# Connectors.net
KiCad netlist of a schematic drawn in Altium Designer
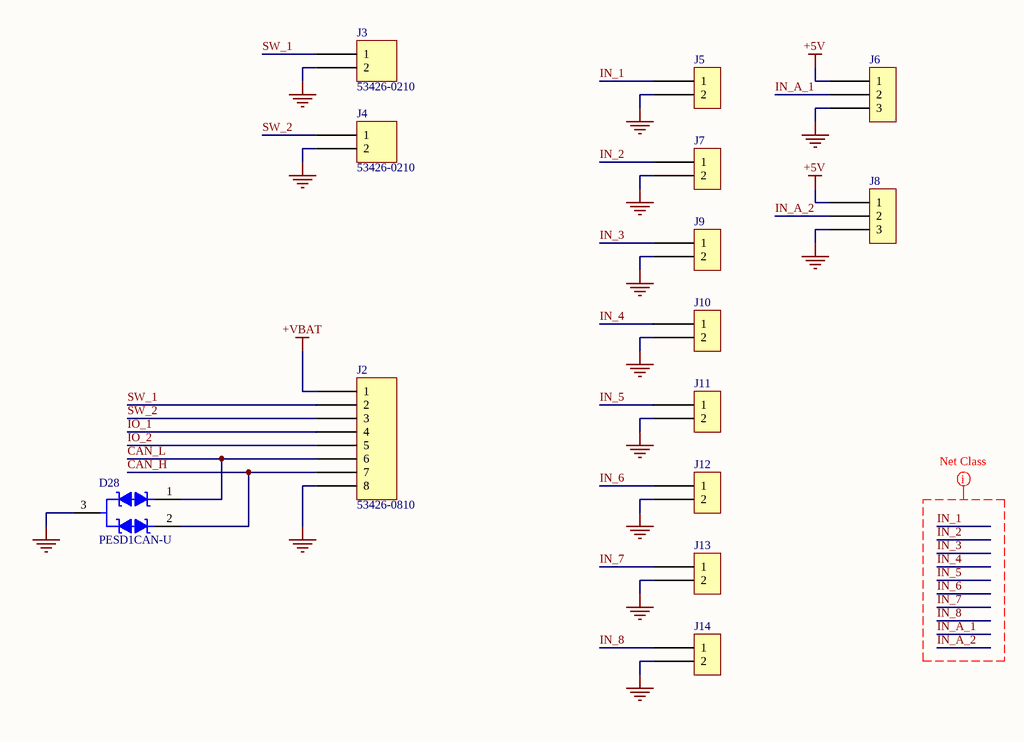
[diagram p0: Connectors.SchDoc]

(export (version "E")
  (design (tool "Eeschema 10.0.6"))
  (components
    (comp (ref "D28")
      (value "PESD1CAN-U")
      (footprint "SOT65P210X110-3N")
      (libsource (lib "CANio") (part "PESD1CAN-U"))
    )
    (comp (ref "J2")
      (value "53426-0810")
      (footprint "53426-0810")
      (description "Molex Mini-Lock™ 53426")
      (libsource (lib "Connectors") (part "53426-0810"))
    )
    (comp (ref "J3")
      (value "53426-0210")
      (footprint "53426-0210")
      (description "Molex Mini-Lock™ 53426")
      (libsource (lib "Connectors") (part "53426-0210"))
    )
    (comp (ref "J4")
      (value "53426-0210")
      (footprint "53426-0210")
      (description "Molex Mini-Lock™ 53426")
      (libsource (lib "Connectors") (part "53426-0210"))
    )
    (comp (ref "J5")
      (value "Wire-2-0.7mm")
      (footprint "WIRE-2-0.7mm")
      (libsource (lib "CANwheel") (part "Wire-2-0.7mm"))
    )
    (comp (ref "J6")
      (value "Wire-3-0.7mm")
      (footprint "WIRE-3-0.7mm")
      (libsource (lib "CANwheel") (part "Wire-3-0.7mm"))
    )
    (comp (ref "J7")
      (value "Wire-2-0.7mm")
      (footprint "WIRE-2-0.7mm")
      (libsource (lib "CANwheel") (part "Wire-2-0.7mm"))
    )
    (comp (ref "J8")
      (value "Wire-3-0.7mm")
      (footprint "WIRE-3-0.7mm")
      (libsource (lib "CANwheel") (part "Wire-3-0.7mm"))
    )
    (comp (ref "J9")
      (value "Wire-2-0.7mm")
      (footprint "WIRE-2-0.7mm")
      (libsource (lib "CANwheel") (part "Wire-2-0.7mm"))
    )
    (comp (ref "J10")
      (value "Wire-2-0.7mm")
      (footprint "WIRE-2-0.7mm")
      (libsource (lib "CANwheel") (part "Wire-2-0.7mm"))
    )
    (comp (ref "J11")
      (value "Wire-2-0.7mm")
      (footprint "WIRE-2-0.7mm")
      (libsource (lib "CANwheel") (part "Wire-2-0.7mm"))
    )
    (comp (ref "J12")
      (value "Wire-2-0.7mm")
      (footprint "WIRE-2-0.7mm")
      (libsource (lib "CANwheel") (part "Wire-2-0.7mm"))
    )
    (comp (ref "J13")
      (value "Wire-2-0.7mm")
      (footprint "WIRE-2-0.7mm")
      (libsource (lib "CANwheel") (part "Wire-2-0.7mm"))
    )
    (comp (ref "J14")
      (value "Wire-2-0.7mm")
      (footprint "WIRE-2-0.7mm")
      (libsource (lib "CANwheel") (part "Wire-2-0.7mm"))
    )
  )
  (nets
    (net (code "1") (name "+5V") (class "Default")
      (node (ref "J6") (pin "1") (pinfunction "1_1") (pintype "passive"))
      (node (ref "J8") (pin "1") (pinfunction "1_1") (pintype "passive"))
    )
    (net (code "2") (name "+VBAT") (class "Default")
      (node (ref "J2") (pin "1") (pinfunction "1_1") (pintype "passive"))
    )
    (net (code "3") (name "/CAN_H") (class "Default")
      (node (ref "D28") (pin "2") (pinfunction "2_2") (pintype "passive"))
      (node (ref "J2") (pin "7") (pinfunction "7_7") (pintype "passive"))
    )
    (net (code "4") (name "/CAN_L") (class "Default")
      (node (ref "D28") (pin "1") (pinfunction "1_1") (pintype "passive"))
      (node (ref "J2") (pin "6") (pinfunction "6_6") (pintype "passive"))
    )
    (net (code "5") (name "/IN_1") (class "Default")
      (node (ref "J5") (pin "1") (pinfunction "1_1") (pintype "passive"))
    )
    (net (code "6") (name "/IN_2") (class "Default")
      (node (ref "J7") (pin "1") (pinfunction "1_1") (pintype "passive"))
    )
    (net (code "7") (name "/IN_3") (class "Default")
      (node (ref "J9") (pin "1") (pinfunction "1_1") (pintype "passive"))
    )
    (net (code "8") (name "/IN_4") (class "Default")
      (node (ref "J10") (pin "1") (pinfunction "1_1") (pintype "passive"))
    )
    (net (code "9") (name "/IN_5") (class "Default")
      (node (ref "J11") (pin "1") (pinfunction "1_1") (pintype "passive"))
    )
    (net (code "10") (name "/IN_6") (class "Default")
      (node (ref "J12") (pin "1") (pinfunction "1_1") (pintype "passive"))
    )
    (net (code "11") (name "/IN_7") (class "Default")
      (node (ref "J13") (pin "1") (pinfunction "1_1") (pintype "passive"))
    )
    (net (code "12") (name "/IN_8") (class "Default")
      (node (ref "J14") (pin "1") (pinfunction "1_1") (pintype "passive"))
    )
    (net (code "13") (name "/IN_A_1") (class "Default")
      (node (ref "J6") (pin "2") (pinfunction "2_2") (pintype "passive"))
    )
    (net (code "14") (name "/IN_A_2") (class "Default")
      (node (ref "J8") (pin "2") (pinfunction "2_2") (pintype "passive"))
    )
    (net (code "15") (name "/IO_1") (class "Default")
      (node (ref "J2") (pin "4") (pinfunction "4_4") (pintype "passive"))
    )
    (net (code "16") (name "/IO_2") (class "Default")
      (node (ref "J2") (pin "5") (pinfunction "5_5") (pintype "passive"))
    )
    (net (code "17") (name "/SW_1") (class "Default")
      (node (ref "J2") (pin "2") (pinfunction "2_2") (pintype "passive"))
      (node (ref "J3") (pin "1") (pinfunction "1_1") (pintype "passive"))
    )
    (net (code "18") (name "/SW_2") (class "Default")
      (node (ref "J2") (pin "3") (pinfunction "3_3") (pintype "passive"))
      (node (ref "J4") (pin "1") (pinfunction "1_1") (pintype "passive"))
    )
    (net (code "19") (name "GND") (class "Default")
      (node (ref "D28") (pin "3") (pinfunction "3_3") (pintype "passive"))
      (node (ref "J10") (pin "2") (pinfunction "2_2") (pintype "passive"))
      (node (ref "J11") (pin "2") (pinfunction "2_2") (pintype "passive"))
      (node (ref "J12") (pin "2") (pinfunction "2_2") (pintype "passive"))
      (node (ref "J13") (pin "2") (pinfunction "2_2") (pintype "passive"))
      (node (ref "J14") (pin "2") (pinfunction "2_2") (pintype "passive"))
      (node (ref "J2") (pin "8") (pinfunction "8_8") (pintype "passive"))
      (node (ref "J3") (pin "2") (pinfunction "2_2") (pintype "passive"))
      (node (ref "J4") (pin "2") (pinfunction "2_2") (pintype "passive"))
      (node (ref "J5") (pin "2") (pinfunction "2_2") (pintype "passive"))
      (node (ref "J6") (pin "3") (pinfunction "3_3") (pintype "passive"))
      (node (ref "J7") (pin "2") (pinfunction "2_2") (pintype "passive"))
      (node (ref "J8") (pin "3") (pinfunction "3_3") (pintype "passive"))
      (node (ref "J9") (pin "2") (pinfunction "2_2") (pintype "passive"))
    )
  )
)
